# ATRACK_KP_V1.net
KiCad netlist of a schematic drawn in Altium Designer
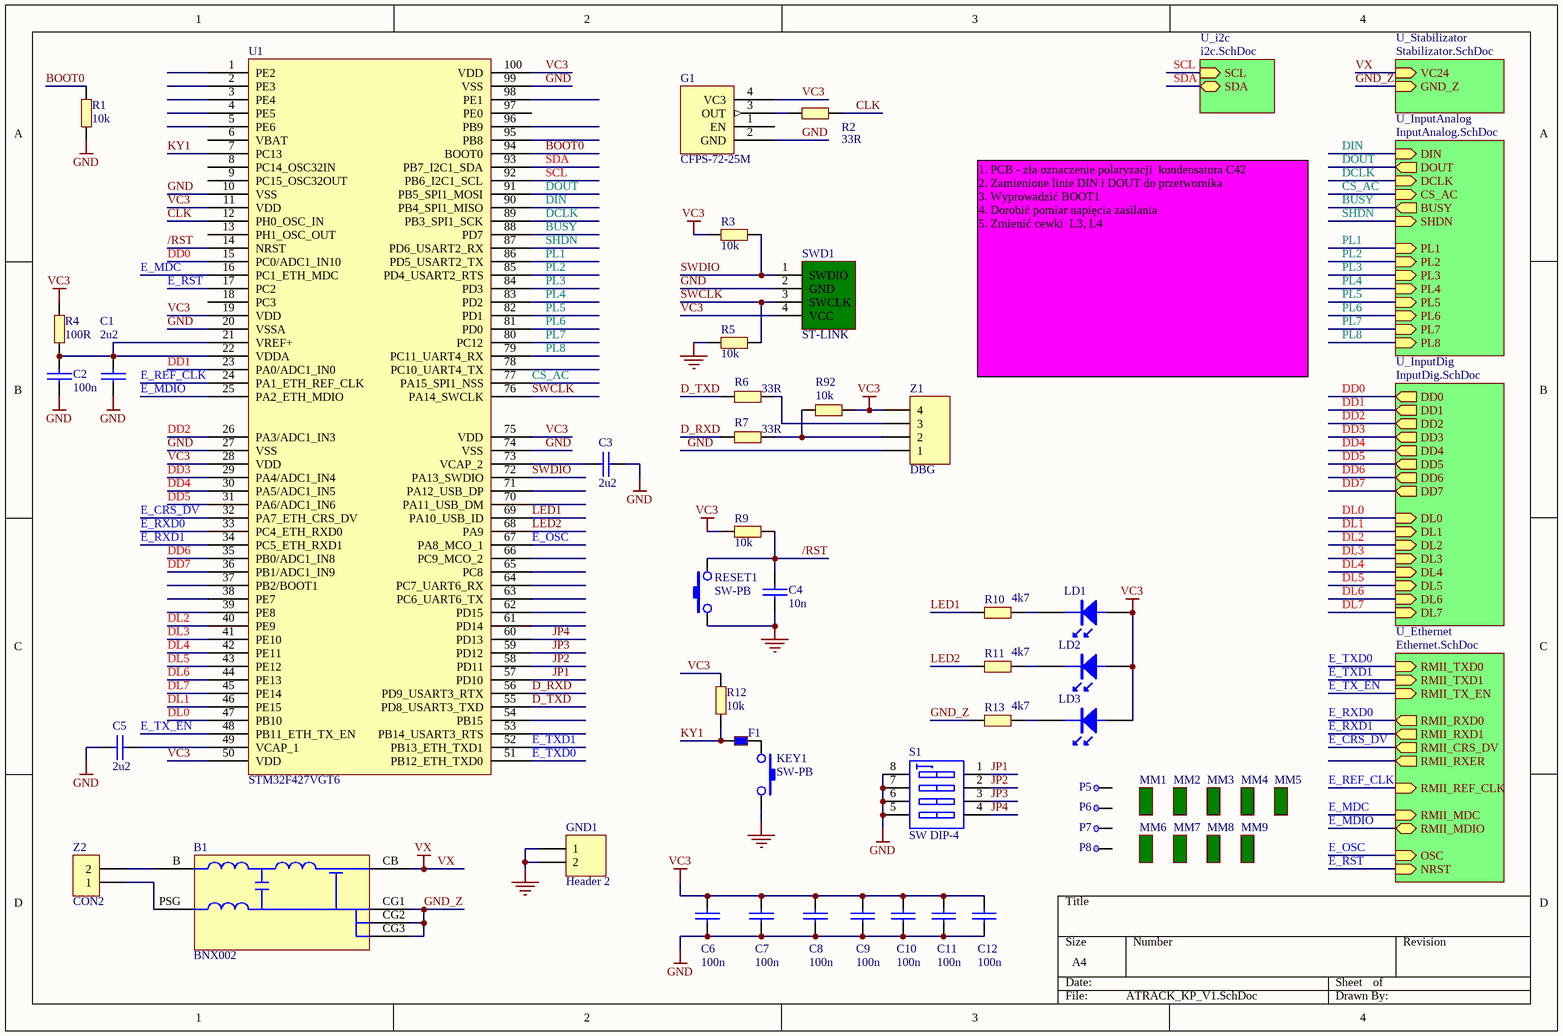
[diagram p0: ATRACK_KP_V1.SchDoc]

(export (version "E")
  (design (tool "Eeschema 10.0.6"))
  (components
    (comp (ref "B1") (value "BNX002") (footprint "BNX002") (libsource (lib "ElhosSchLib") (part "BNX002")))
    (comp (ref "C1")
      (value "2u2")
      (footprint "0603C")
      (description "Capacitor")
      (libsource (lib "*") (part "CAP"))
    )
    (comp (ref "C2")
      (value "100n")
      (footprint "0603C")
      (description "Capacitor")
      (libsource (lib "*") (part "CAP"))
    )
    (comp (ref "C3")
      (value "2u2")
      (footprint "0603C")
      (description "Capacitor")
      (libsource (lib "*") (part "CAP"))
    )
    (comp (ref "C4")
      (value "10n")
      (footprint "0603C")
      (description "Capacitor")
      (libsource (lib "*") (part "CAP"))
    )
    (comp (ref "C5")
      (value "2u2")
      (footprint "0603C")
      (description "Capacitor")
      (libsource (lib "*") (part "CAP"))
    )
    (comp (ref "C6")
      (value "100n")
      (footprint "0603C")
      (description "Capacitor")
      (libsource (lib "*") (part "CAP"))
    )
    (comp (ref "C7")
      (value "100n")
      (footprint "0603C")
      (description "Capacitor")
      (libsource (lib "*") (part "CAP"))
    )
    (comp (ref "C8")
      (value "100n")
      (footprint "0603C")
      (description "Capacitor")
      (libsource (lib "*") (part "CAP"))
    )
    (comp (ref "C9")
      (value "100n")
      (footprint "0603C")
      (description "Capacitor")
      (libsource (lib "*") (part "CAP"))
    )
    (comp (ref "C10")
      (value "100n")
      (footprint "0603C")
      (description "Capacitor")
      (libsource (lib "*") (part "CAP"))
    )
    (comp (ref "C11")
      (value "100n")
      (footprint "0603C")
      (description "Capacitor")
      (libsource (lib "*") (part "CAP"))
    )
    (comp (ref "C12")
      (value "100n")
      (footprint "0603C")
      (description "Capacitor")
      (libsource (lib "*") (part "CAP"))
    )
    (comp (ref "F1")
      (value "BLM18BB141SN1D")
      (footprint "0603L")
      (description "Koralik ferrytowy")
      (libsource (lib "*") (part "1812"))
    )
    (comp (ref "G1") (value "CFPS-72-25M") (footprint "GEN_SMD1_1") (libsource (lib "*") (part "GENER_SMD")))
    (comp (ref "GND1")
      (value "Header 2")
      (footprint "HDR1X2")
      (description "Header, 2-Pin")
      (fields (field (name "PUBLISHER") "Altium Limited"))
      (libsource (lib "Miscellaneous Connectors") (part "Header 2"))
    )
    (comp (ref "KEY1") (value "SW-PB") (footprint "DTSM31N_2") (libsource (lib "*") (part "SW-PB")))
    (comp (ref "LD1") (value "~") (footprint "0603DG") (libsource (lib "*") (part "LED")))
    (comp (ref "LD2") (value "~") (footprint "0603DR") (libsource (lib "*") (part "LED")))
    (comp (ref "LD3") (value "~") (footprint "0603DG") (libsource (lib "*") (part "LED")))
    (comp (ref "MM1") (value "~") (footprint "REF_CIR") (libsource (lib "*") (part "MECH")))
    (comp (ref "MM2") (value "~") (footprint "REF_CIR") (libsource (lib "*") (part "MECH")))
    (comp (ref "MM3") (value "~") (footprint "REF_SQR") (libsource (lib "*") (part "MECH")))
    (comp (ref "MM4") (value "~") (footprint "REF_SQR") (libsource (lib "*") (part "MECH")))
    (comp (ref "MM5") (value "~") (footprint "PB_FREE_GRAF") (libsource (lib "*") (part "MECH")))
    (comp (ref "MM6") (value "~") (footprint "REF_CIR") (libsource (lib "*") (part "MECH")))
    (comp (ref "MM7") (value "~") (footprint "REF_CIR") (libsource (lib "*") (part "MECH")))
    (comp (ref "MM8") (value "~") (footprint "REF_SQR") (libsource (lib "*") (part "MECH")))
    (comp (ref "MM9") (value "~") (footprint "REF_SQR") (libsource (lib "*") (part "MECH")))
    (comp (ref "P5") (value "PP") (footprint "PP_SR") (libsource (lib "*") (part "PP")))
    (comp (ref "P6") (value "PP") (footprint "PP_SR") (libsource (lib "*") (part "PP")))
    (comp (ref "P7") (value "PP") (footprint "PP_SR") (libsource (lib "*") (part "PP")))
    (comp (ref "P8") (value "PP") (footprint "PP_SR") (libsource (lib "*") (part "PP")))
    (comp (ref "R1") (value "10k") (footprint "0603R") (libsource (lib "") (part "RES3_3")))
    (comp (ref "R2") (value "33R") (footprint "0603R") (libsource (lib "") (part "RES3_2")))
    (comp (ref "R3") (value "10k") (footprint "0603R") (libsource (lib "*") (part "RES3")))
    (comp (ref "R4") (value "100R") (footprint "0603R") (libsource (lib "") (part "RES3_2")))
    (comp (ref "R5") (value "10k") (footprint "0603R") (libsource (lib "*") (part "RES3")))
    (comp (ref "R6") (value "33R") (footprint "0603R") (libsource (lib "") (part "RES3_1")))
    (comp (ref "R7") (value "33R") (footprint "0603R") (libsource (lib "") (part "RES3_1")))
    (comp (ref "R9") (value "10k") (footprint "0603R") (libsource (lib "*") (part "RES3")))
    (comp (ref "R10") (value "4k7") (footprint "0603R") (libsource (lib "") (part "RES3_1")))
    (comp (ref "R11") (value "4k7") (footprint "0603R") (libsource (lib "") (part "RES3_1")))
    (comp (ref "R12") (value "10k") (footprint "0603R") (libsource (lib "") (part "RES3_2")))
    (comp (ref "R13") (value "4k7") (footprint "0603R") (libsource (lib "") (part "RES3_1")))
    (comp (ref "R92") (value "10k") (footprint "0603R") (libsource (lib "*") (part "RES3")))
    (comp (ref "RESET1") (value "SW-PB") (footprint "DTSM31N_2") (libsource (lib "*") (part "SW-PB")))
    (comp (ref "S1")
      (value "SW DIP-4")
      (footprint "DIP8-SW")
      (description "DIP Switch")
      (libsource (lib "*") (part "SW DIP-4"))
    )
    (comp (ref "SWD1")
      (value "ST-LINK")
      (footprint "PIN4")
      (description "Header, 4-Pin")
      (fields (field (name "PUBLISHER") "Altium Limited"))
      (libsource (lib "GkSchlib") (part "SW_CON"))
    )
    (comp (ref "U1")
      (value "STM32F427VGT6")
      (footprint "VQ100_2")
      (libsource (lib "GkSchlib") (part "STM32F427_LQFP100"))
    )
    (comp (ref "Z1")
      (value "DBG")
      (footprint "PIN4")
      (description "Header, 4-Pin")
      (fields (field (name "PUBLISHER") "Altium Limited"))
      (libsource (lib "Miscellaneous Connectors") (part "Header 4"))
    )
    (comp (ref "Z2")
      (value "CON2")
      (footprint "ARC-2-5.08-A1")
      (description "Connector")
      (libsource (lib "*") (part "CON2"))
    )
  )
  (nets
    (net (code "1") (name "/BOOT0") (class "Default")
      (node (ref "R1") (pin "1") (pintype "passive"))
      (node (ref "U1") (pin "94") (pinfunction "BOOT0_94") (pintype "passive"))
    )
    (net (code "2") (name "/BUSY") (class "Default")
      (node (ref "U1") (pin "88") (pinfunction "PD7_88") (pintype "passive"))
    )
    (net (code "3") (name "/CLK") (class "Default")
      (node (ref "R2") (pin "2") (pintype "passive"))
      (node (ref "U1") (pin "12") (pinfunction "PH0_OSC_IN_12") (pintype "passive"))
    )
    (net (code "4") (name "/CS_AC") (class "Default")
      (node (ref "U1") (pin "77") (pinfunction "PA15_SPI1_NSS_77") (pintype "passive"))
    )
    (net (code "5") (name "/DCLK") (class "Default")
      (node (ref "U1") (pin "89") (pinfunction "PB3_SPI1_SCK_89") (pintype "passive"))
    )
    (net (code "6") (name "/DD0") (class "Default")
      (node (ref "U1") (pin "15") (pinfunction "PC0/ADC1_IN10_15") (pintype "passive"))
    )
    (net (code "7") (name "/DD1") (class "Default")
      (node (ref "U1") (pin "23") (pinfunction "PA0/ADC1_IN0_23") (pintype "passive"))
    )
    (net (code "8") (name "/DD2") (class "Default")
      (node (ref "U1") (pin "26") (pinfunction "PA3/ADC1_IN3_26") (pintype "passive"))
    )
    (net (code "9") (name "/DD3") (class "Default")
      (node (ref "U1") (pin "29") (pinfunction "PA4/ADC1_IN4_29") (pintype "passive"))
    )
    (net (code "10") (name "/DD4") (class "Default")
      (node (ref "U1") (pin "30") (pinfunction "PA5/ADC1_IN5_30") (pintype "passive"))
    )
    (net (code "11") (name "/DD5") (class "Default")
      (node (ref "U1") (pin "31") (pinfunction "PA6/ADC1_IN6_31") (pintype "passive"))
    )
    (net (code "12") (name "/DD6") (class "Default")
      (node (ref "U1") (pin "35") (pinfunction "PB0/ADC1_IN8_35") (pintype "passive"))
    )
    (net (code "13") (name "/DD7") (class "Default")
      (node (ref "U1") (pin "36") (pinfunction "PB1/ADC1_IN9_36") (pintype "passive"))
    )
    (net (code "14") (name "/DIN") (class "Default")
      (node (ref "U1") (pin "90") (pinfunction "PB4_SPI1_MISO_90") (pintype "passive"))
    )
    (net (code "15") (name "/DL0") (class "Default")
      (node (ref "U1") (pin "47") (pinfunction "PB10_47") (pintype "passive"))
    )
    (net (code "16") (name "/DL1") (class "Default")
      (node (ref "U1") (pin "46") (pinfunction "PE15_46") (pintype "passive"))
    )
    (net (code "17") (name "/DL2") (class "Default")
      (node (ref "U1") (pin "40") (pinfunction "PE9_40") (pintype "passive"))
    )
    (net (code "18") (name "/DL3") (class "Default")
      (node (ref "U1") (pin "41") (pinfunction "PE10_41") (pintype "passive"))
    )
    (net (code "19") (name "/DL4") (class "Default")
      (node (ref "U1") (pin "42") (pinfunction "PE11_42") (pintype "passive"))
    )
    (net (code "20") (name "/DL5") (class "Default")
      (node (ref "U1") (pin "43") (pinfunction "PE12_43") (pintype "passive"))
    )
    (net (code "21") (name "/DL6") (class "Default")
      (node (ref "U1") (pin "44") (pinfunction "PE13_44") (pintype "passive"))
    )
    (net (code "22") (name "/DL7") (class "Default")
      (node (ref "U1") (pin "45") (pinfunction "PE14_45") (pintype "passive"))
    )
    (net (code "23") (name "/DOUT") (class "Default")
      (node (ref "U1") (pin "91") (pinfunction "PB5_SPI1_MOSI_91") (pintype "passive"))
    )
    (net (code "24") (name "/D_RXD") (class "Default")
      (node (ref "R7") (pin "2") (pintype "passive"))
      (node (ref "U1") (pin "56") (pinfunction "PD9_USART3_RTX_56") (pintype "passive"))
    )
    (net (code "25") (name "/D_TXD") (class "Default")
      (node (ref "R6") (pin "2") (pintype "passive"))
      (node (ref "U1") (pin "55") (pinfunction "PD8_USART3_TXD_55") (pintype "passive"))
    )
    (net (code "26") (name "/E_CRS_DV") (class "Default")
      (node (ref "U1") (pin "32") (pinfunction "PA7_ETH_CRS_DV_32") (pintype "passive"))
    )
    (net (code "27") (name "/E_MDC") (class "Default")
      (node (ref "U1") (pin "16") (pinfunction "PC1_ETH_MDC_16") (pintype "passive"))
    )
    (net (code "28") (name "/E_MDIO") (class "Default")
      (node (ref "U1") (pin "25") (pinfunction "PA2_ETH_MDIO_25") (pintype "passive"))
    )
    (net (code "29") (name "/E_OSC") (class "Default")
      (node (ref "U1") (pin "67") (pinfunction "PA8_MCO_1_67") (pintype "passive"))
    )
    (net (code "30") (name "/E_REF_CLK") (class "Default")
      (node (ref "U1") (pin "24") (pinfunction "PA1_ETH_REF_CLK_24") (pintype "passive"))
    )
    (net (code "31") (name "/E_RST") (class "Default")
      (node (ref "U1") (pin "17") (pinfunction "PC2_17") (pintype "passive"))
    )
    (net (code "32") (name "/E_RXD0") (class "Default")
      (node (ref "U1") (pin "33") (pinfunction "PC4_ETH_RXD0_33") (pintype "passive"))
    )
    (net (code "33") (name "/E_RXD1") (class "Default")
      (node (ref "U1") (pin "34") (pinfunction "PC5_ETH_RXD1_34") (pintype "passive"))
    )
    (net (code "34") (name "/E_TXD0") (class "Default")
      (node (ref "U1") (pin "51") (pinfunction "PB12_ETH_TXD0_51") (pintype "passive"))
    )
    (net (code "35") (name "/E_TXD1") (class "Default")
      (node (ref "U1") (pin "52") (pinfunction "PB13_ETH_TXD1_52") (pintype "passive"))
    )
    (net (code "36") (name "/E_TX_EN") (class "Default")
      (node (ref "U1") (pin "48") (pinfunction "PB11_ETH_TX_EN_48") (pintype "passive"))
    )
    (net (code "37") (name "/GND_Z") (class "Default")
      (node (ref "B1") (pin "CG1") (pintype "passive"))
      (node (ref "B1") (pin "CG2") (pintype "passive"))
      (node (ref "B1") (pin "CG3") (pintype "passive"))
      (node (ref "R13") (pin "2") (pintype "passive"))
    )
    (net (code "38") (name "/JP1") (class "Default")
      (node (ref "S1") (pin "1") (pinfunction "A1_1") (pintype "passive"))
      (node (ref "U1") (pin "57") (pinfunction "PD10_57") (pintype "passive"))
    )
    (net (code "39") (name "/JP2") (class "Default")
      (node (ref "S1") (pin "2") (pinfunction "A2_2") (pintype "passive"))
      (node (ref "U1") (pin "58") (pinfunction "PD11_58") (pintype "passive"))
    )
    (net (code "40") (name "/JP3") (class "Default")
      (node (ref "S1") (pin "3") (pinfunction "A3_3") (pintype "passive"))
      (node (ref "U1") (pin "59") (pinfunction "PD12_59") (pintype "passive"))
    )
    (net (code "41") (name "/JP4") (class "Default")
      (node (ref "S1") (pin "4") (pinfunction "A4_4") (pintype "passive"))
      (node (ref "U1") (pin "60") (pinfunction "PD13_60") (pintype "passive"))
    )
    (net (code "42") (name "/KY1") (class "Default")
      (node (ref "F1") (pin "2") (pintype "passive"))
      (node (ref "R12") (pin "1") (pintype "passive"))
      (node (ref "U1") (pin "7") (pinfunction "PC13_7") (pintype "passive"))
    )
    (net (code "43") (name "/LED1") (class "Default")
      (node (ref "R10") (pin "2") (pintype "passive"))
      (node (ref "U1") (pin "69") (pinfunction "PA10_USB_ID_69") (pintype "passive"))
    )
    (net (code "44") (name "/LED2") (class "Default")
      (node (ref "R11") (pin "2") (pintype "passive"))
      (node (ref "U1") (pin "68") (pinfunction "PA9_68") (pintype "passive"))
    )
    (net (code "45") (name "/PL1") (class "Default")
      (node (ref "U1") (pin "86") (pinfunction "PD5_USART2_TX_86") (pintype "passive"))
    )
    (net (code "46") (name "/PL2") (class "Default")
      (node (ref "U1") (pin "85") (pinfunction "PD4_USART2_RTS_85") (pintype "passive"))
    )
    (net (code "47") (name "/PL3") (class "Default")
      (node (ref "U1") (pin "84") (pinfunction "PD3_84") (pintype "passive"))
    )
    (net (code "48") (name "/PL4") (class "Default")
      (node (ref "U1") (pin "83") (pinfunction "PD2_83") (pintype "passive"))
    )
    (net (code "49") (name "/PL5") (class "Default")
      (node (ref "U1") (pin "82") (pinfunction "PD1_82") (pintype "passive"))
    )
    (net (code "50") (name "/PL6") (class "Default")
      (node (ref "U1") (pin "81") (pinfunction "PD0_81") (pintype "passive"))
    )
    (net (code "51") (name "/PL7") (class "Default")
      (node (ref "U1") (pin "80") (pinfunction "PC12_80") (pintype "passive"))
    )
    (net (code "52") (name "/PL8") (class "Default")
      (node (ref "U1") (pin "79") (pinfunction "PC11_UART4_RX_79") (pintype "passive"))
    )
    (net (code "54") (name "/SCL") (class "Default")
      (node (ref "U1") (pin "92") (pinfunction "PB6_I2C1_SCL_92") (pintype "passive"))
    )
    (net (code "55") (name "/SDA") (class "Default")
      (node (ref "U1") (pin "93") (pinfunction "PB7_I2C1_SDA_93") (pintype "passive"))
    )
    (net (code "56") (name "/SHDN") (class "Default")
      (node (ref "U1") (pin "87") (pinfunction "PD6_USART2_RX_87") (pintype "passive"))
    )
    (net (code "57") (name "/SWCLK") (class "Default")
      (node (ref "R5") (pin "2") (pintype "passive"))
      (node (ref "SWD1") (pin "3") (pinfunction "SWCLK_3") (pintype "passive"))
      (node (ref "U1") (pin "76") (pinfunction "PA14_SWCLK_76") (pintype "passive"))
    )
    (net (code "58") (name "/SWDIO") (class "Default")
      (node (ref "R3") (pin "2") (pintype "passive"))
      (node (ref "SWD1") (pin "1") (pinfunction "SWDIO_1") (pintype "passive"))
      (node (ref "U1") (pin "72") (pinfunction "PA13_SWDIO_72") (pintype "passive"))
    )
    (net (code "59") (name "/{slash}RST") (class "Default")
      (node (ref "C4") (pin "1") (pinfunction "1_1") (pintype "passive"))
      (node (ref "R9") (pin "2") (pintype "passive"))
      (node (ref "RESET1") (pin "2") (pinfunction "2_2") (pintype "passive"))
      (node (ref "U1") (pin "14") (pinfunction "NRST_14") (pintype "passive"))
    )
    (net (code "60") (name "GND") (class "Default")
      (node (ref "C1") (pin "2") (pinfunction "2_2") (pintype "passive"))
      (node (ref "C10") (pin "2") (pinfunction "2_2") (pintype "passive"))
      (node (ref "C11") (pin "2") (pinfunction "2_2") (pintype "passive"))
      (node (ref "C12") (pin "2") (pinfunction "2_2") (pintype "passive"))
      (node (ref "C2") (pin "2") (pinfunction "2_2") (pintype "passive"))
      (node (ref "C3") (pin "1") (pinfunction "1_1") (pintype "passive"))
      (node (ref "C4") (pin "2") (pinfunction "2_2") (pintype "passive"))
      (node (ref "C5") (pin "1") (pinfunction "1_1") (pintype "passive"))
      (node (ref "C6") (pin "2") (pinfunction "2_2") (pintype "passive"))
      (node (ref "C7") (pin "2") (pinfunction "2_2") (pintype "passive"))
      (node (ref "C8") (pin "2") (pinfunction "2_2") (pintype "passive"))
      (node (ref "C9") (pin "2") (pinfunction "2_2") (pintype "passive"))
      (node (ref "G1") (pin "2") (pinfunction "GND_2") (pintype "power_in"))
      (node (ref "GND1") (pin "1") (pinfunction "1_1") (pintype "passive"))
      (node (ref "GND1") (pin "2") (pinfunction "2_2") (pintype "passive"))
      (node (ref "KEY1") (pin "2") (pinfunction "2_2") (pintype "passive"))
      (node (ref "R1") (pin "2") (pintype "passive"))
      (node (ref "R5") (pin "1") (pintype "passive"))
      (node (ref "RESET1") (pin "1") (pinfunction "1_1") (pintype "passive"))
      (node (ref "S1") (pin "5") (pinfunction "B4_5") (pintype "passive"))
      (node (ref "S1") (pin "6") (pinfunction "B3_6") (pintype "passive"))
      (node (ref "S1") (pin "7") (pinfunction "B2_7") (pintype "passive"))
      (node (ref "S1") (pin "8") (pinfunction "B1_8") (pintype "passive"))
      (node (ref "SWD1") (pin "2") (pinfunction "GND_2") (pintype "passive"))
      (node (ref "U1") (pin "10") (pinfunction "VSS_10") (pintype "passive"))
      (node (ref "U1") (pin "20") (pinfunction "VSSA_20") (pintype "passive"))
      (node (ref "U1") (pin "27") (pinfunction "VSS_27") (pintype "passive"))
      (node (ref "U1") (pin "74") (pinfunction "VSS_74") (pintype "passive"))
      (node (ref "U1") (pin "99") (pinfunction "VSS_99") (pintype "passive"))
      (node (ref "Z1") (pin "1") (pinfunction "1_1") (pintype "passive"))
    )
    (net (code "61") (name "Net-(B1-PadB)") (class "Default")
      (node (ref "B1") (pin "B") (pintype "passive"))
      (node (ref "Z2") (pin "2") (pinfunction "2_2") (pintype "passive"))
    )
    (net (code "62") (name "Net-(B1-PadPSG)") (class "Default")
      (node (ref "B1") (pin "PSG") (pintype "passive"))
      (node (ref "Z2") (pin "1") (pinfunction "1_1") (pintype "passive"))
    )
    (net (code "63") (name "Net-(F1-Pad1)") (class "Default")
      (node (ref "F1") (pin "1") (pintype "passive"))
      (node (ref "KEY1") (pin "1") (pinfunction "1_1") (pintype "passive"))
    )
    (net (code "64") (name "Net-(G1-OUT)") (class "Default")
      (node (ref "G1") (pin "3") (pinfunction "OUT_3") (pintype "output"))
      (node (ref "R2") (pin "1") (pintype "passive"))
    )
    (net (code "65") (name "Net-(LD1-2)") (class "Default")
      (node (ref "LD1") (pin "K") (pinfunction "2_K") (pintype "passive"))
      (node (ref "R10") (pin "1") (pintype "passive"))
    )
    (net (code "66") (name "Net-(LD2-2)") (class "Default")
      (node (ref "LD2") (pin "K") (pinfunction "2_K") (pintype "passive"))
      (node (ref "R11") (pin "1") (pintype "passive"))
    )
    (net (code "67") (name "Net-(LD3-2)") (class "Default")
      (node (ref "LD3") (pin "K") (pinfunction "2_K") (pintype "passive"))
      (node (ref "R13") (pin "1") (pintype "passive"))
    )
    (net (code "68") (name "Net-(R6-Pad1)") (class "Default")
      (node (ref "R6") (pin "1") (pintype "passive"))
      (node (ref "Z1") (pin "3") (pinfunction "3_3") (pintype "passive"))
    )
    (net (code "69") (name "Net-(R7-Pad1)") (class "Default")
      (node (ref "R7") (pin "1") (pintype "passive"))
      (node (ref "R92") (pin "1") (pintype "passive"))
      (node (ref "Z1") (pin "2") (pinfunction "2_2") (pintype "passive"))
    )
    (net (code "70") (name "Net-(U1-VCAP_1)") (class "Default")
      (node (ref "C5") (pin "2") (pinfunction "2_2") (pintype "passive"))
      (node (ref "U1") (pin "49") (pinfunction "VCAP_1_49") (pintype "passive"))
    )
    (net (code "71") (name "Net-(U1-VCAP_2)") (class "Default")
      (node (ref "C3") (pin "2") (pinfunction "2_2") (pintype "passive"))
      (node (ref "U1") (pin "73") (pinfunction "VCAP_2_73") (pintype "passive"))
    )
    (net (code "72") (name "Net-(U1-VDDA)") (class "Default")
      (node (ref "C1") (pin "1") (pinfunction "1_1") (pintype "passive"))
      (node (ref "C2") (pin "1") (pinfunction "1_1") (pintype "passive"))
      (node (ref "R4") (pin "1") (pintype "passive"))
      (node (ref "U1") (pin "21") (pinfunction "VREF+_21") (pintype "passive"))
      (node (ref "U1") (pin "22") (pinfunction "VDDA_22") (pintype "passive"))
    )
    (net (code "73") (name "VC3") (class "Default")
      (node (ref "C10") (pin "1") (pinfunction "1_1") (pintype "passive"))
      (node (ref "C11") (pin "1") (pinfunction "1_1") (pintype "passive"))
      (node (ref "C12") (pin "1") (pinfunction "1_1") (pintype "passive"))
      (node (ref "C6") (pin "1") (pinfunction "1_1") (pintype "passive"))
      (node (ref "C7") (pin "1") (pinfunction "1_1") (pintype "passive"))
      (node (ref "C8") (pin "1") (pinfunction "1_1") (pintype "passive"))
      (node (ref "C9") (pin "1") (pinfunction "1_1") (pintype "passive"))
      (node (ref "G1") (pin "4") (pinfunction "VC3_4") (pintype "power_in"))
      (node (ref "LD1") (pin "A") (pinfunction "1_A") (pintype "passive"))
      (node (ref "LD2") (pin "A") (pinfunction "1_A") (pintype "passive"))
      (node (ref "LD3") (pin "A") (pinfunction "1_A") (pintype "passive"))
      (node (ref "R12") (pin "2") (pintype "passive"))
      (node (ref "R3") (pin "1") (pintype "passive"))
      (node (ref "R4") (pin "2") (pintype "passive"))
      (node (ref "R9") (pin "1") (pintype "passive"))
      (node (ref "R92") (pin "2") (pintype "passive"))
      (node (ref "SWD1") (pin "4") (pinfunction "VCC_4") (pintype "passive"))
      (node (ref "U1") (pin "100") (pinfunction "VDD_100") (pintype "passive"))
      (node (ref "U1") (pin "11") (pinfunction "VDD_11") (pintype "passive"))
      (node (ref "U1") (pin "19") (pinfunction "VDD_19") (pintype "passive"))
      (node (ref "U1") (pin "28") (pinfunction "VDD_28") (pintype "passive"))
      (node (ref "U1") (pin "50") (pinfunction "VDD_50") (pintype "passive"))
      (node (ref "U1") (pin "75") (pinfunction "VDD_75") (pintype "passive"))
      (node (ref "Z1") (pin "4") (pinfunction "4_4") (pintype "passive"))
    )
    (net (code "74") (name "VX") (class "Default") (node (ref "B1") (pin "CB") (pintype "passive")))
    (net (code "75") (name "unconnected-(G1-EN-Pad1)") (class "Default")
      (node (ref "G1") (pin "1") (pinfunction "EN_1") (pintype "passive"))
    )
    (net (code "76") (name "unconnected-(P5-Pad1)") (class "Default")
      (node (ref "P5") (pin "1") (pintype "passive"))
    )
    (net (code "77") (name "unconnected-(P6-Pad1)") (class "Default")
      (node (ref "P6") (pin "1") (pintype "passive"))
    )
    (net (code "78") (name "unconnected-(P7-Pad1)") (class "Default")
      (node (ref "P7") (pin "1") (pintype "passive"))
    )
    (net (code "79") (name "unconnected-(P8-Pad1)") (class "Default")
      (node (ref "P8") (pin "1") (pintype "passive"))
    )
    (net (code "80") (name "unconnected-(U1-PA11_USB_DM-Pad70)") (class "Default")
      (node (ref "U1") (pin "70") (pinfunction "PA11_USB_DM_70") (pintype "passive"))
    )
    (net (code "81") (name "unconnected-(U1-PA12_USB_DP-Pad71)") (class "Default")
      (node (ref "U1") (pin "71") (pinfunction "PA12_USB_DP_71") (pintype "passive"))
    )
    (net (code "82") (name "unconnected-(U1-PB2{slash}BOOT1-Pad37)") (class "Default")
      (node (ref "U1") (pin "37") (pinfunction "PB2/BOOT1_37") (pintype "passive"))
    )
    (net (code "83") (name "unconnected-(U1-PB8-Pad95)") (class "Default")
      (node (ref "U1") (pin "95") (pinfunction "PB8_95") (pintype "passive"))
    )
    (net (code "84") (name "unconnected-(U1-PB9-Pad96)") (class "Default")
      (node (ref "U1") (pin "96") (pinfunction "PB9_96") (pintype "passive"))
    )
    (net (code "85") (name "unconnected-(U1-PB14_USART3_RTS-Pad53)") (class "Default")
      (node (ref "U1") (pin "53") (pinfunction "PB14_USART3_RTS_53") (pintype "passive"))
    )
    (net (code "86") (name "unconnected-(U1-PB15-Pad54)") (class "Default")
      (node (ref "U1") (pin "54") (pinfunction "PB15_54") (pintype "passive"))
    )
    (net (code "87") (name "unconnected-(U1-PC3-Pad18)") (class "Default")
      (node (ref "U1") (pin "18") (pinfunction "PC3_18") (pintype "passive"))
    )
    (net (code "88") (name "unconnected-(U1-PC6_UART6_TX-Pad63)") (class "Default")
      (node (ref "U1") (pin "63") (pinfunction "PC6_UART6_TX_63") (pintype "passive"))
    )
    (net (code "89") (name "unconnected-(U1-PC7_UART6_RX-Pad64)") (class "Default")
      (node (ref "U1") (pin "64") (pinfunction "PC7_UART6_RX_64") (pintype "passive"))
    )
    (net (code "90") (name "unconnected-(U1-PC8-Pad65)") (class "Default")
      (node (ref "U1") (pin "65") (pinfunction "PC8_65") (pintype "passive"))
    )
    (net (code "91") (name "unconnected-(U1-PC9_MCO_2-Pad66)") (class "Default")
      (node (ref "U1") (pin "66") (pinfunction "PC9_MCO_2_66") (pintype "passive"))
    )
    (net (code "92") (name "unconnected-(U1-PC10_UART4_TX-Pad78)") (class "Default")
      (node (ref "U1") (pin "78") (pinfunction "PC10_UART4_TX_78") (pintype "passive"))
    )
    (net (code "93") (name "unconnected-(U1-PC14_OSC32IN-Pad8)") (class "Default")
      (node (ref "U1") (pin "8") (pinfunction "PC14_OSC32IN_8") (pintype "passive"))
    )
    (net (code "94") (name "unconnected-(U1-PC15_OSC32OUT-Pad9)") (class "Default")
      (node (ref "U1") (pin "9") (pinfunction "PC15_OSC32OUT_9") (pintype "passive"))
    )
    (net (code "95") (name "unconnected-(U1-PD14-Pad61)") (class "Default")
      (node (ref "U1") (pin "61") (pinfunction "PD14_61") (pintype "passive"))
    )
    (net (code "96") (name "unconnected-(U1-PD15-Pad62)") (class "Default")
      (node (ref "U1") (pin "62") (pinfunction "PD15_62") (pintype "passive"))
    )
    (net (code "97") (name "unconnected-(U1-PE0-Pad97)") (class "Default")
      (node (ref "U1") (pin "97") (pinfunction "PE0_97") (pintype "passive"))
    )
    (net (code "98") (name "unconnected-(U1-PE1-Pad98)") (class "Default")
      (node (ref "U1") (pin "98") (pinfunction "PE1_98") (pintype "passive"))
    )
    (net (code "99") (name "unconnected-(U1-PE2-Pad1)") (class "Default")
      (node (ref "U1") (pin "1") (pinfunction "PE2_1") (pintype "passive"))
    )
    (net (code "100") (name "unconnected-(U1-PE3-Pad2)") (class "Default")
      (node (ref "U1") (pin "2") (pinfunction "PE3_2") (pintype "passive"))
    )
    (net (code "101") (name "unconnected-(U1-PE4-Pad3)") (class "Default")
      (node (ref "U1") (pin "3") (pinfunction "PE4_3") (pintype "passive"))
    )
    (net (code "102") (name "unconnected-(U1-PE5-Pad4)") (class "Default")
      (node (ref "U1") (pin "4") (pinfunction "PE5_4") (pintype "passive"))
    )
    (net (code "103") (name "unconnected-(U1-PE6-Pad5)") (class "Default")
      (node (ref "U1") (pin "5") (pinfunction "PE6_5") (pintype "passive"))
    )
    (net (code "104") (name "unconnected-(U1-PE7-Pad38)") (class "Default")
      (node (ref "U1") (pin "38") (pinfunction "PE7_38") (pintype "passive"))
    )
    (net (code "105") (name "unconnected-(U1-PE8-Pad39)") (class "Default")
      (node (ref "U1") (pin "39") (pinfunction "PE8_39") (pintype "passive"))
    )
    (net (code "106") (name "unconnected-(U1-PH1_OSC_OUT-Pad13)") (class "Default")
      (node (ref "U1") (pin "13") (pinfunction "PH1_OSC_OUT_13") (pintype "passive"))
    )
    (net (code "107") (name "unconnected-(U1-VBAT-Pad6)") (class "Default")
      (node (ref "U1") (pin "6") (pinfunction "VBAT_6") (pintype "passive"))
    )
  )
)
